# ProPrj_tachoConverter_2025-10-29.net
KiCad netlist of a schematic drawn in EasyEDA Pro
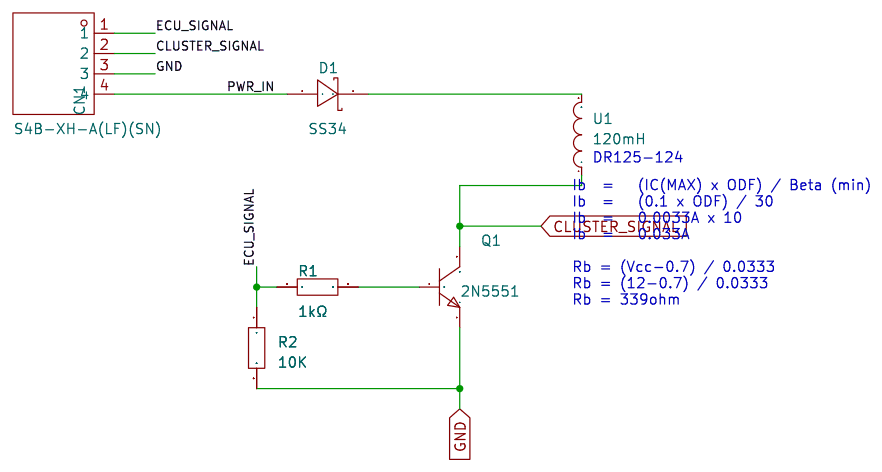
[diagram p0: schematic sheet]

(export (version "E")
  (design (tool "Eeschema 10.0.6"))
  (components
    (comp (ref "CN1")
      (value "S4B-XH-A(LF)(SN)")
      (footprint "easyedapro:CONN-TH_S4B-XH-A-LF-SN")
      (fields (field (name "Manufacturer") "JST"))
      (libsource (lib "easyedapro") (part "S4B-XH-A (LF)(SN)"))
    )
    (comp (ref "D1")
      (value "SS34")
      (footprint "easyedapro:SMA_L4.3-W2.6-LS5.2-RD")
      (fields (field (name "Manufacturer") "MDD(辰达半导体)"))
      (libsource (lib "easyedapro") (part "SS34_C8678"))
    )
    (comp (ref "Q1")
      (value "2N5551")
      (footprint "easyedapro:SOT-23-3_L2.9-W1.4-P1.90-LS2.5-BR")
      (fields (field (name "Manufacturer") "RUILON(瑞隆源)"))
      (libsource (lib "easyedapro") (part "2N5551_C7529570"))
    )
    (comp (ref "R1")
      (value "1kΩ")
      (footprint "easyedapro:R0603")
      (fields
        (field (name "Manufacturer Part") "0603WAF1001T5E")
        (field (name "Manufacturer") "UNI-ROYAL(厚声)")
      )
      (libsource (lib "easyedapro") (part "0603WAF1001T5E"))
    )
    (comp (ref "R2") (value "10K") (footprint "easyedapro:R0603") (libsource (lib "easyedapro") (part "Res")))
    (comp (ref "U1")
      (value "120mH")
      (footprint "easyedapro:IND-SMD_L12.5-W12.5")
      (fields (field (name "Manufacturer Part") "DR125-124-R") (field (name "Manufacturer") "EATON(伊顿)"))
      (libsource (lib "easyedapro") (part "DR125-124-R"))
    )
  )
  (nets
    (net (code "1") (name "/ECU_SIGNAL") (class "Default")
      (node (ref "CN1") (pin "1") (pinfunction "1_1") (pintype "unspecified"))
      (node (ref "R1") (pin "1") (pinfunction "1_1") (pintype "input"))
      (node (ref "R2") (pin "1") (pinfunction "1_1") (pintype "input"))
    )
    (net (code "2") (name "/PWR_IN") (class "Default")
      (node (ref "CN1") (pin "4") (pinfunction "4_4") (pintype "unspecified"))
      (node (ref "D1") (pin "2") (pinfunction "A_2") (pintype "unspecified"))
    )
    (net (code "3") (name "CLUSTER_SIGNAL") (class "Default")
      (node (ref "CN1") (pin "2") (pinfunction "2_2") (pintype "unspecified"))
      (node (ref "Q1") (pin "3") (pinfunction "C_3") (pintype "unspecified"))
      (node (ref "U1") (pin "1") (pinfunction "1_1") (pintype "unspecified"))
    )
    (net (code "4") (name "GND") (class "Default")
      (node (ref "CN1") (pin "3") (pinfunction "3_3") (pintype "unspecified"))
      (node (ref "Q1") (pin "2") (pinfunction "E_2") (pintype "unspecified"))
      (node (ref "R2") (pin "2") (pinfunction "2_2") (pintype "input"))
    )
    (net (code "5") (name "Net-(D1-K)") (class "Default")
      (node (ref "D1") (pin "1") (pinfunction "K_1") (pintype "unspecified"))
      (node (ref "U1") (pin "2") (pinfunction "2_2") (pintype "unspecified"))
    )
    (net (code "6") (name "Net-(Q1-B)") (class "Default")
      (node (ref "Q1") (pin "1") (pinfunction "B_1") (pintype "unspecified"))
      (node (ref "R1") (pin "2") (pinfunction "2_2") (pintype "input"))
    )
  )
)
